# STM32_MCU.net
KiCad netlist of a schematic drawn in Altium Designer
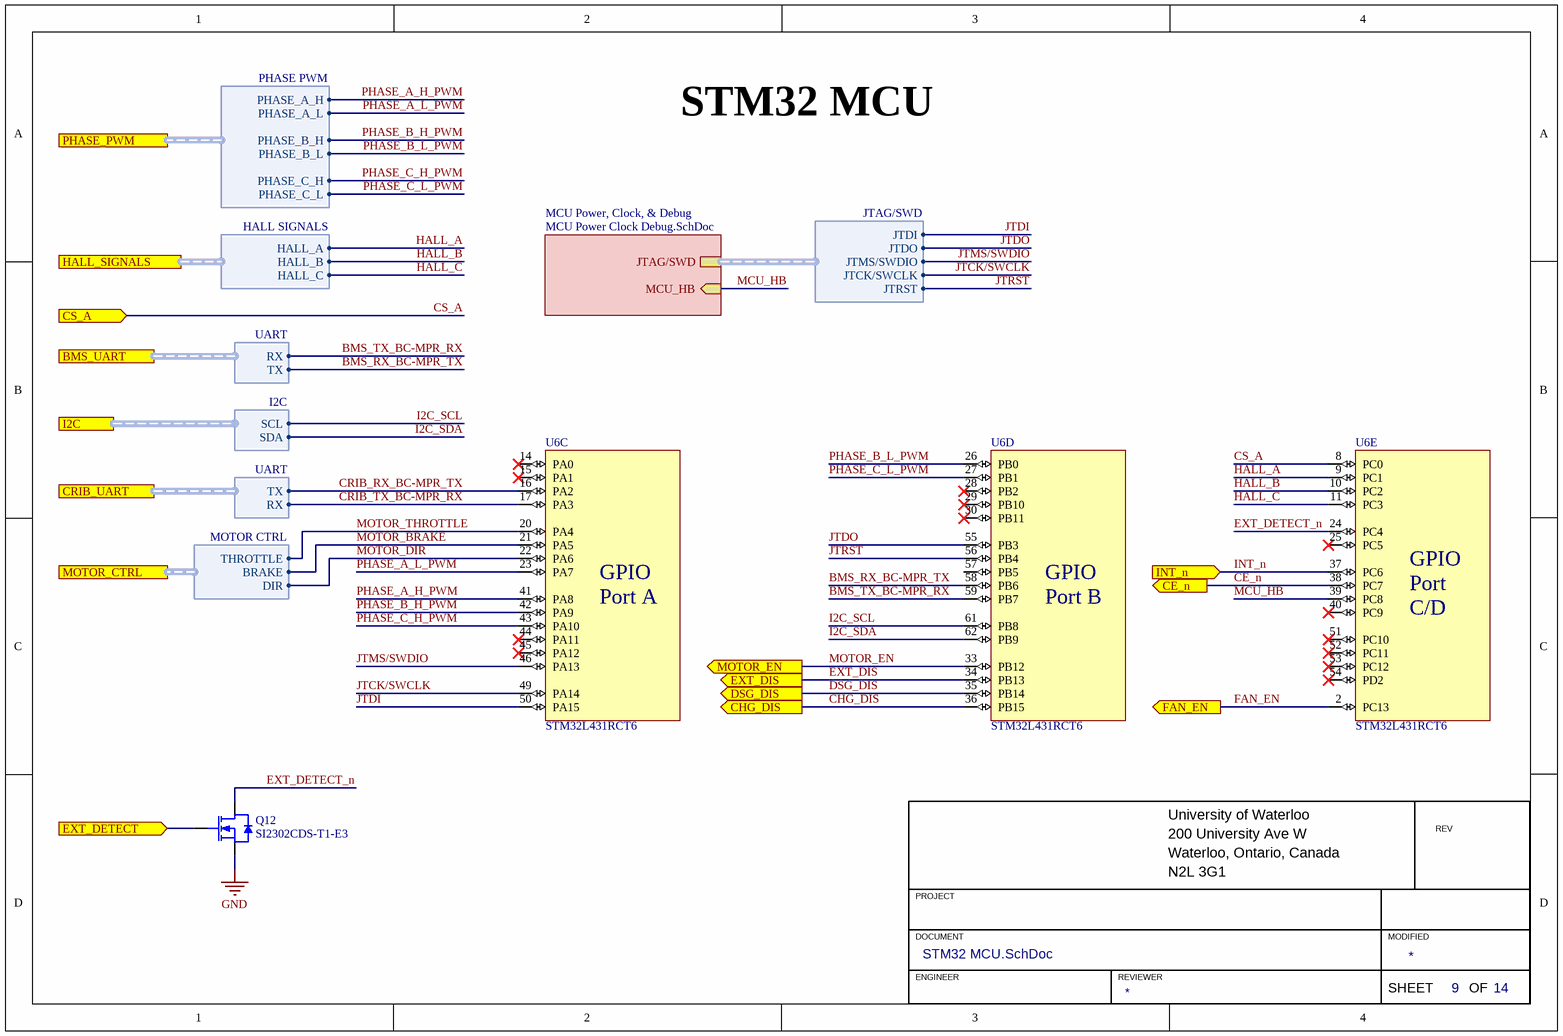
[diagram p0: STM32 MCU.SchDoc]

(export (version "E")
  (design (tool "Eeschema 10.0.6"))
  (components
    (comp (ref "Q12")
      (value "NMOS_20V_6A")
      (footprint "SOT23-3")
      (description "MOSFET N-CH 20V 2.6A SOT23-3")
      (fields (field (name "MANUFACTURER PART NUMBER 1") "SI2302CDS-T1-E3"))
      (libsource (lib "Personal_Schematic_Library_2022") (part "NMOS_20V_2.6A"))
    )
    (comp (ref "U6")
      (value "STM32L431RCT6")
      (footprint "STM_LQFP64")
      (description "IC MCU 32BIT 256KB FLASH 64LQFP")
      (libsource (lib "Personal_Schematic_Library_2022") (part "STM32L431RCT6"))
    )
  )
  (nets
    (net (code "10") (name "/BMS_RX_BC-MPR_TX") (class "Default")
      (node (ref "U6") (pin "58") (pinfunction "PB6_58") (pintype "bidirectional"))
    )
    (net (code "11") (name "/BMS_TX_BC-MPR_RX") (class "Default")
      (node (ref "U6") (pin "59") (pinfunction "PB7_59") (pintype "bidirectional"))
    )
    (net (code "12") (name "/CE_n") (class "Default")
      (node (ref "U6") (pin "38") (pinfunction "PC7_38") (pintype "bidirectional"))
    )
    (net (code "13") (name "/CHG_DIS") (class "Default")
      (node (ref "U6") (pin "36") (pinfunction "PB15_36") (pintype "bidirectional"))
    )
    (net (code "14") (name "/CRIB_RX_BC-MPR_TX") (class "Default")
      (node (ref "U6") (pin "16") (pinfunction "PA2_16") (pintype "bidirectional"))
    )
    (net (code "15") (name "/CRIB_TX_BC-MPR_RX") (class "Default")
      (node (ref "U6") (pin "17") (pinfunction "PA3_17") (pintype "bidirectional"))
    )
    (net (code "16") (name "/CS_A") (class "Default")
      (node (ref "U6") (pin "8") (pinfunction "PC0_8") (pintype "bidirectional"))
    )
    (net (code "17") (name "/DSG_DIS") (class "Default")
      (node (ref "U6") (pin "35") (pinfunction "PB14_35") (pintype "bidirectional"))
    )
    (net (code "18") (name "/EXT_DETECT") (class "Default")
      (node (ref "Q12") (pin "1") (pinfunction "GATE_1") (pintype "passive"))
    )
    (net (code "19") (name "/EXT_DETECT_n") (class "Default")
      (node (ref "Q12") (pin "3") (pinfunction "DRAIN_3") (pintype "passive"))
      (node (ref "U6") (pin "24") (pinfunction "PC4_24") (pintype "bidirectional"))
    )
    (net (code "20") (name "/EXT_DIS") (class "Default")
      (node (ref "U6") (pin "34") (pinfunction "PB13_34") (pintype "bidirectional"))
    )
    (net (code "21") (name "/FAN_EN") (class "Default")
      (node (ref "U6") (pin "2") (pinfunction "PC13_2") (pintype "bidirectional"))
    )
    (net (code "22") (name "/HALL_A") (class "Default")
      (node (ref "U6") (pin "9") (pinfunction "PC1_9") (pintype "bidirectional"))
    )
    (net (code "23") (name "/HALL_B") (class "Default")
      (node (ref "U6") (pin "10") (pinfunction "PC2_10") (pintype "bidirectional"))
    )
    (net (code "24") (name "/HALL_C") (class "Default")
      (node (ref "U6") (pin "11") (pinfunction "PC3_11") (pintype "bidirectional"))
    )
    (net (code "25") (name "/I2C_SCL") (class "Default")
      (node (ref "U6") (pin "61") (pinfunction "PB8_61") (pintype "bidirectional"))
    )
    (net (code "26") (name "/I2C_SDA") (class "Default")
      (node (ref "U6") (pin "62") (pinfunction "PB9_62") (pintype "bidirectional"))
    )
    (net (code "27") (name "/INT_n") (class "Default")
      (node (ref "U6") (pin "37") (pinfunction "PC6_37") (pintype "bidirectional"))
    )
    (net (code "28") (name "/JTCK{slash}SWCLK") (class "Default")
      (node (ref "U6") (pin "49") (pinfunction "PA14_49") (pintype "bidirectional"))
    )
    (net (code "29") (name "/JTDI") (class "Default")
      (node (ref "U6") (pin "50") (pinfunction "PA15_50") (pintype "bidirectional"))
    )
    (net (code "30") (name "/JTDO") (class "Default")
      (node (ref "U6") (pin "55") (pinfunction "PB3_55") (pintype "bidirectional"))
    )
    (net (code "31") (name "/JTMS{slash}SWDIO") (class "Default")
      (node (ref "U6") (pin "46") (pinfunction "PA13_46") (pintype "bidirectional"))
    )
    (net (code "32") (name "/JTRST") (class "Default")
      (node (ref "U6") (pin "56") (pinfunction "PB4_56") (pintype "bidirectional"))
    )
    (net (code "33") (name "/MCU_HB") (class "Default")
      (node (ref "U6") (pin "39") (pinfunction "PC8_39") (pintype "bidirectional"))
    )
    (net (code "34") (name "/MOTOR_BRAKE") (class "Default")
      (node (ref "U6") (pin "21") (pinfunction "PA5_21") (pintype "bidirectional"))
    )
    (net (code "35") (name "/MOTOR_DIR") (class "Default")
      (node (ref "U6") (pin "22") (pinfunction "PA6_22") (pintype "bidirectional"))
    )
    (net (code "36") (name "/MOTOR_EN") (class "Default")
      (node (ref "U6") (pin "33") (pinfunction "PB12_33") (pintype "bidirectional"))
    )
    (net (code "37") (name "/MOTOR_THROTTLE") (class "Default")
      (node (ref "U6") (pin "20") (pinfunction "PA4_20") (pintype "bidirectional"))
    )
    (net (code "38") (name "/PHASE_A_H_PWM") (class "Default")
      (node (ref "U6") (pin "41") (pinfunction "PA8_41") (pintype "bidirectional"))
    )
    (net (code "39") (name "/PHASE_A_L_PWM") (class "Default")
      (node (ref "U6") (pin "23") (pinfunction "PA7_23") (pintype "bidirectional"))
    )
    (net (code "40") (name "/PHASE_B_H_PWM") (class "Default")
      (node (ref "U6") (pin "42") (pinfunction "PA9_42") (pintype "bidirectional"))
    )
    (net (code "41") (name "/PHASE_B_L_PWM") (class "Default")
      (node (ref "U6") (pin "26") (pinfunction "PB0_26") (pintype "bidirectional"))
    )
    (net (code "42") (name "/PHASE_C_H_PWM") (class "Default")
      (node (ref "U6") (pin "43") (pinfunction "PA10_43") (pintype "bidirectional"))
    )
    (net (code "43") (name "/PHASE_C_L_PWM") (class "Default")
      (node (ref "U6") (pin "27") (pinfunction "PB1_27") (pintype "bidirectional"))
    )
    (net (code "50") (name "GND") (class "Default")
      (node (ref "Q12") (pin "2") (pinfunction "SOURCE_2") (pintype "passive"))
    )
    (net (code "51") (name "unconnected-(U6C-PA0-Pad14)") (class "Default")
      (node (ref "U6") (pin "14") (pinfunction "PA0_14") (pintype "bidirectional+no_connect"))
    )
    (net (code "52") (name "unconnected-(U6C-PA1-Pad15)") (class "Default")
      (node (ref "U6") (pin "15") (pinfunction "PA1_15") (pintype "bidirectional+no_connect"))
    )
    (net (code "53") (name "unconnected-(U6C-PA11-Pad44)") (class "Default")
      (node (ref "U6") (pin "44") (pinfunction "PA11_44") (pintype "bidirectional+no_connect"))
    )
    (net (code "54") (name "unconnected-(U6C-PA12-Pad45)") (class "Default")
      (node (ref "U6") (pin "45") (pinfunction "PA12_45") (pintype "bidirectional+no_connect"))
    )
    (net (code "55") (name "unconnected-(U6D-PB2-Pad28)") (class "Default")
      (node (ref "U6") (pin "28") (pinfunction "PB2_28") (pintype "bidirectional+no_connect"))
    )
    (net (code "56") (name "unconnected-(U6D-PB5-Pad57)") (class "Default")
      (node (ref "U6") (pin "57") (pinfunction "PB5_57") (pintype "bidirectional"))
    )
    (net (code "57") (name "unconnected-(U6D-PB10-Pad29)") (class "Default")
      (node (ref "U6") (pin "29") (pinfunction "PB10_29") (pintype "bidirectional+no_connect"))
    )
    (net (code "58") (name "unconnected-(U6D-PB11-Pad30)") (class "Default")
      (node (ref "U6") (pin "30") (pinfunction "PB11_30") (pintype "bidirectional+no_connect"))
    )
    (net (code "59") (name "unconnected-(U6E-PC5-Pad25)") (class "Default")
      (node (ref "U6") (pin "25") (pinfunction "PC5_25") (pintype "bidirectional+no_connect"))
    )
    (net (code "60") (name "unconnected-(U6E-PC9-Pad40)") (class "Default")
      (node (ref "U6") (pin "40") (pinfunction "PC9_40") (pintype "bidirectional+no_connect"))
    )
    (net (code "61") (name "unconnected-(U6E-PC10-Pad51)") (class "Default")
      (node (ref "U6") (pin "51") (pinfunction "PC10_51") (pintype "bidirectional+no_connect"))
    )
    (net (code "62") (name "unconnected-(U6E-PC11-Pad52)") (class "Default")
      (node (ref "U6") (pin "52") (pinfunction "PC11_52") (pintype "bidirectional+no_connect"))
    )
    (net (code "63") (name "unconnected-(U6E-PC12-Pad53)") (class "Default")
      (node (ref "U6") (pin "53") (pinfunction "PC12_53") (pintype "bidirectional+no_connect"))
    )
    (net (code "64") (name "unconnected-(U6E-PD2-Pad54)") (class "Default")
      (node (ref "U6") (pin "54") (pinfunction "PD2_54") (pintype "bidirectional+no_connect"))
    )
  )
)
